# uC.net
KiCad netlist of a schematic drawn in Altium Designer
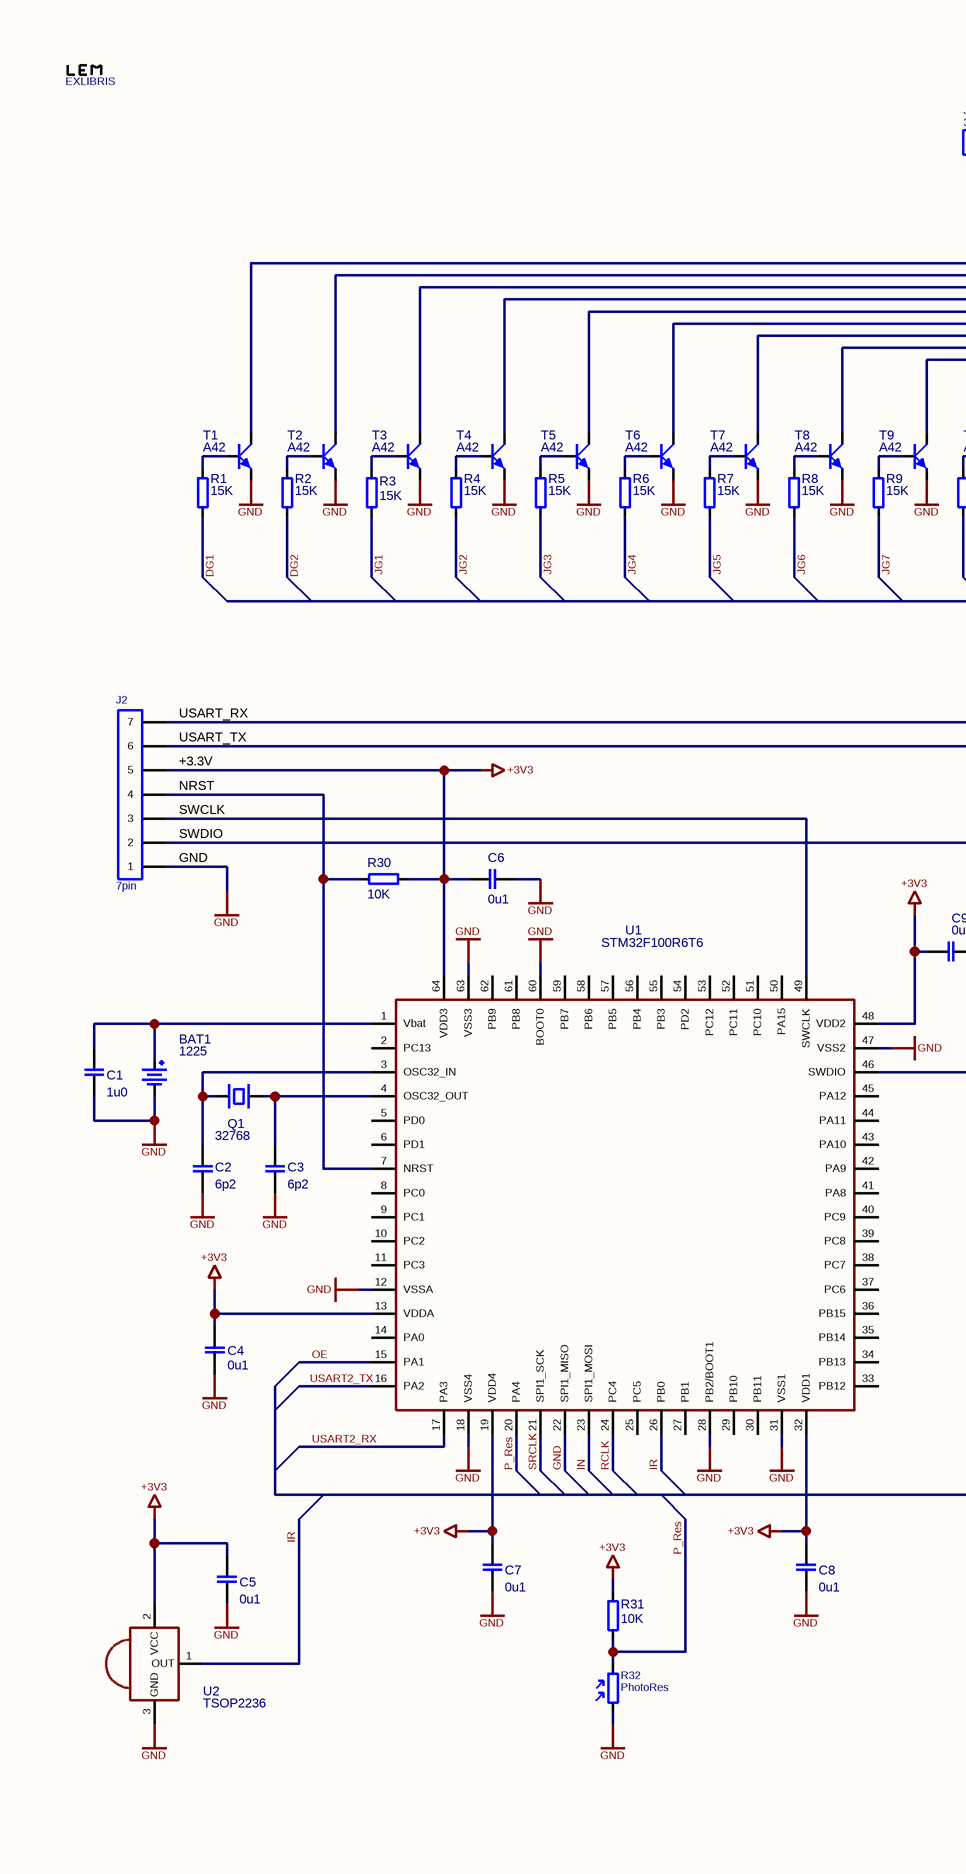
[diagram p0: uC.SchDoc, left]
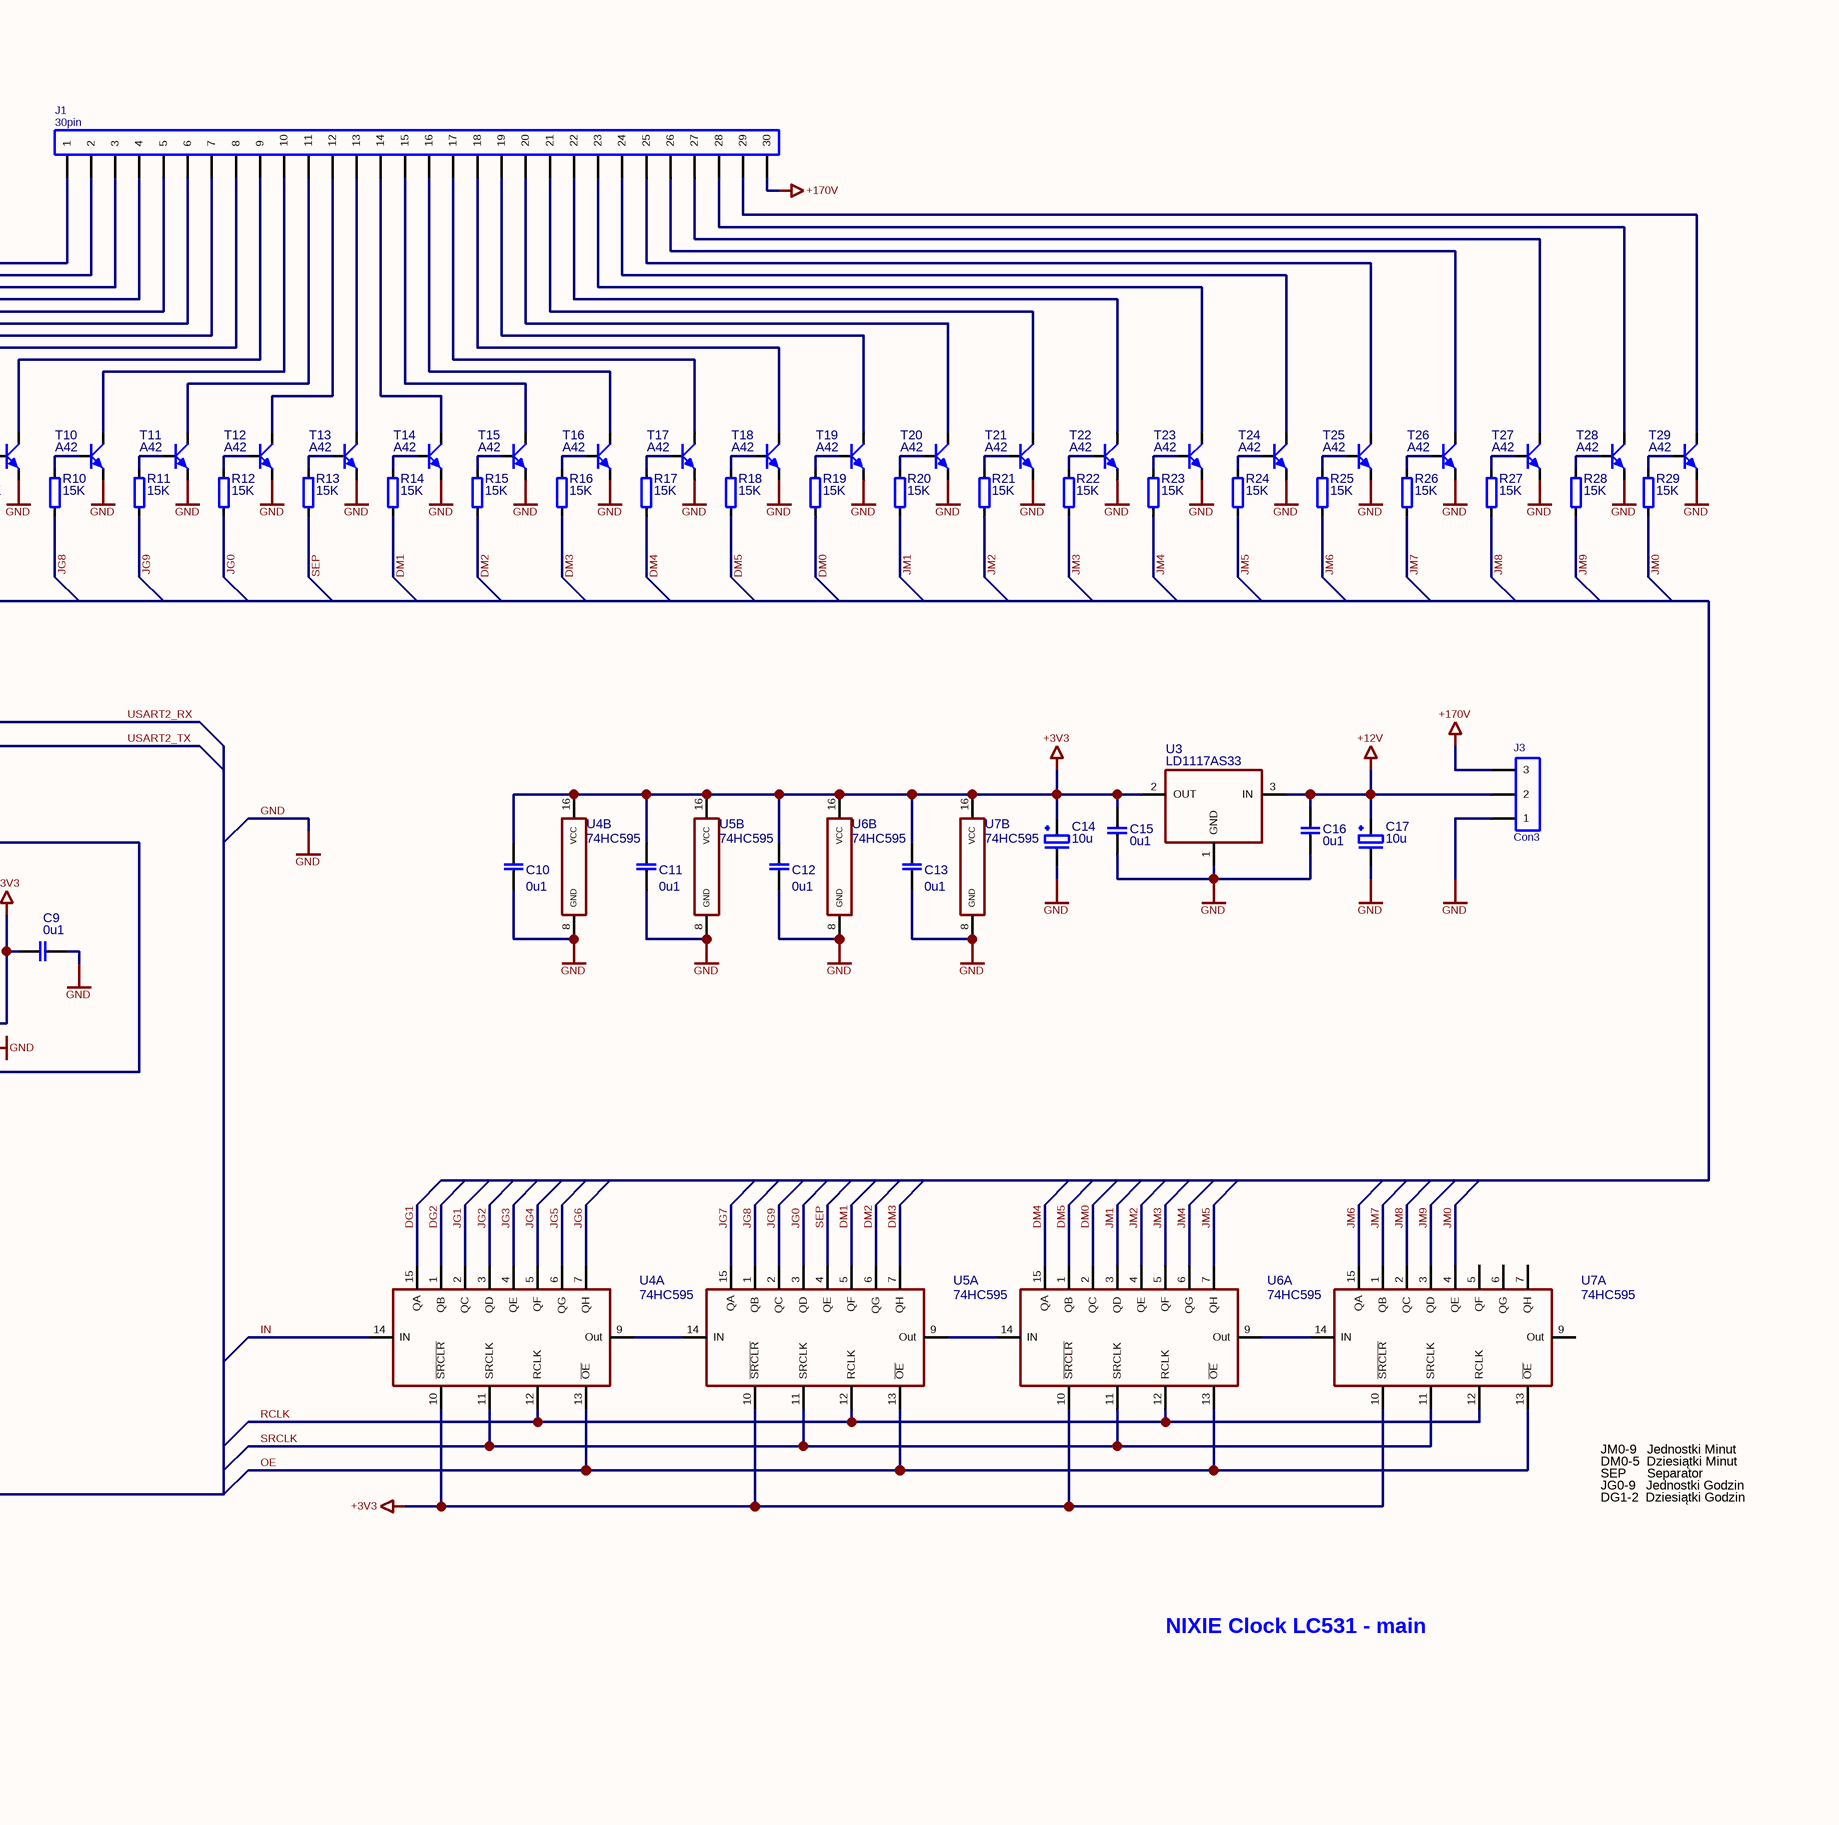
[diagram p1: uC.SchDoc, right]

(export (version "E")
  (design (tool "Eeschema 10.0.6"))
  (components
    (comp (ref "BAT1")
      (value "1225")
      (footprint "SMTU-1225")
      (description "Bateria Litowa 3V")
      (libsource (lib "Sch_Passive") (part "BAT_3V"))
    )
    (comp (ref "C1")
      (value "1u0")
      (footprint "C_SMD_0805")
      (description "Kondensator monolityczny")
      (libsource (lib "Caps") (part "C"))
    )
    (comp (ref "C2")
      (value "6p2")
      (footprint "C_SMD_0805")
      (description "Kondensator monolityczny")
      (libsource (lib "Caps") (part "C"))
    )
    (comp (ref "C3")
      (value "6p2")
      (footprint "C_SMD_0805")
      (description "Kondensator monolityczny")
      (libsource (lib "Caps") (part "C"))
    )
    (comp (ref "C4")
      (value "0u1")
      (footprint "C_SMD_0603")
      (description "Kondensator monolityczny")
      (libsource (lib "Caps") (part "C"))
    )
    (comp (ref "C5")
      (value "0u1")
      (footprint "C_SMD_0603")
      (description "Kondensator monolityczny")
      (libsource (lib "Caps") (part "C"))
    )
    (comp (ref "C6")
      (value "0u1")
      (footprint "C_SMD_0603")
      (description "Kondensator monolityczny")
      (libsource (lib "Caps") (part "C"))
    )
    (comp (ref "C7")
      (value "0u1")
      (footprint "C_SMD_0603")
      (description "Kondensator monolityczny")
      (libsource (lib "Caps") (part "C"))
    )
    (comp (ref "C8")
      (value "0u1")
      (footprint "C_SMD_0603")
      (description "Kondensator monolityczny")
      (libsource (lib "Caps") (part "C"))
    )
    (comp (ref "C9")
      (value "0u1")
      (footprint "C_SMD_0603")
      (description "Kondensator monolityczny")
      (libsource (lib "Caps") (part "C"))
    )
    (comp (ref "C10")
      (value "0u1")
      (footprint "C_SMD_0603")
      (description "Kondensator monolityczny")
      (libsource (lib "Caps") (part "C"))
    )
    (comp (ref "C11")
      (value "0u1")
      (footprint "C_SMD_0603")
      (description "Kondensator monolityczny")
      (libsource (lib "Caps") (part "C"))
    )
    (comp (ref "C12")
      (value "0u1")
      (footprint "C_SMD_0603")
      (description "Kondensator monolityczny")
      (libsource (lib "Caps") (part "C"))
    )
    (comp (ref "C13")
      (value "0u1")
      (footprint "C_SMD_0603")
      (description "Kondensator monolityczny")
      (libsource (lib "Caps") (part "C"))
    )
    (comp (ref "C14")
      (value "10u")
      (footprint "CE_T_SMC_6032_28")
      (description "Kondensator elektrolityczny")
      (libsource (lib "Caps") (part "CE"))
    )
    (comp (ref "C15")
      (value "0u1")
      (footprint "C_SMD_0603")
      (description "Kondensator monolityczny")
      (libsource (lib "Caps") (part "C"))
    )
    (comp (ref "C16")
      (value "0u1")
      (footprint "C_SMD_0603")
      (description "Kondensator monolityczny")
      (libsource (lib "Caps") (part "C"))
    )
    (comp (ref "C17")
      (value "10u")
      (footprint "CE_T_SMC_6032_28")
      (description "Kondensator elektrolityczny")
      (libsource (lib "Caps") (part "CE"))
    )
    (comp (ref "EXLIBRIS") (value "EXLIBRIS") (footprint "EXLBS_2") (libsource (lib "Misc") (part "EXLBR")))
    (comp (ref "J1") (value "30pin") (footprint "SIL30") (libsource (lib "Connectors") (part "CON 30pin")))
    (comp (ref "J2")
      (value "7pin")
      (footprint "SIL7_SMD_Horizontal")
      (description "Connector 7pin")
      (libsource (lib "Connectors") (part "CON 7pin"))
    )
    (comp (ref "J3")
      (value "Con3")
      (footprint "TE_147323-2")
      (description "Connector 3pin")
      (libsource (lib "Connectors") (part "CON 3pin"))
    )
    (comp (ref "Q1")
      (value "32768")
      (footprint "XTAL_3")
      (description "Rezonator kwarcowy")
      (libsource (lib "Sch_Passive") (part "Q"))
    )
    (comp (ref "R1")
      (value "15K")
      (footprint "R_SMD_0603")
      (description "Resistor")
      (libsource (lib "Res") (part "R"))
    )
    (comp (ref "R2")
      (value "15K")
      (footprint "R_SMD_0603")
      (description "Resistor")
      (libsource (lib "Res") (part "R"))
    )
    (comp (ref "R3")
      (value "15K")
      (footprint "R_SMD_0603")
      (description "Resistor")
      (libsource (lib "Res") (part "R"))
    )
    (comp (ref "R4")
      (value "15K")
      (footprint "R_SMD_0603")
      (description "Resistor")
      (libsource (lib "Res") (part "R"))
    )
    (comp (ref "R5")
      (value "15K")
      (footprint "R_SMD_0603")
      (description "Resistor")
      (libsource (lib "Res") (part "R"))
    )
    (comp (ref "R6")
      (value "15K")
      (footprint "R_SMD_0603")
      (description "Resistor")
      (libsource (lib "Res") (part "R"))
    )
    (comp (ref "R7")
      (value "15K")
      (footprint "R_SMD_0603")
      (description "Resistor")
      (libsource (lib "Res") (part "R"))
    )
    (comp (ref "R8")
      (value "15K")
      (footprint "R_SMD_0603")
      (description "Resistor")
      (libsource (lib "Res") (part "R"))
    )
    (comp (ref "R9")
      (value "15K")
      (footprint "R_SMD_0603")
      (description "Resistor")
      (libsource (lib "Res") (part "R"))
    )
    (comp (ref "R10")
      (value "15K")
      (footprint "R_SMD_0603")
      (description "Resistor")
      (libsource (lib "Res") (part "R"))
    )
    (comp (ref "R11")
      (value "15K")
      (footprint "R_SMD_0603")
      (description "Resistor")
      (libsource (lib "Res") (part "R"))
    )
    (comp (ref "R12")
      (value "15K")
      (footprint "R_SMD_0603")
      (description "Resistor")
      (libsource (lib "Res") (part "R"))
    )
    (comp (ref "R13")
      (value "15K")
      (footprint "R_SMD_0603")
      (description "Resistor")
      (libsource (lib "Res") (part "R"))
    )
    (comp (ref "R14")
      (value "15K")
      (footprint "R_SMD_0603")
      (description "Resistor")
      (libsource (lib "Res") (part "R"))
    )
    (comp (ref "R15")
      (value "15K")
      (footprint "R_SMD_0603")
      (description "Resistor")
      (libsource (lib "Res") (part "R"))
    )
    (comp (ref "R16")
      (value "15K")
      (footprint "R_SMD_0603")
      (description "Resistor")
      (libsource (lib "Res") (part "R"))
    )
    (comp (ref "R17")
      (value "15K")
      (footprint "R_SMD_0603")
      (description "Resistor")
      (libsource (lib "Res") (part "R"))
    )
    (comp (ref "R18")
      (value "15K")
      (footprint "R_SMD_0603")
      (description "Resistor")
      (libsource (lib "Res") (part "R"))
    )
    (comp (ref "R19")
      (value "15K")
      (footprint "R_SMD_0603")
      (description "Resistor")
      (libsource (lib "Res") (part "R"))
    )
    (comp (ref "R20")
      (value "15K")
      (footprint "R_SMD_0603")
      (description "Resistor")
      (libsource (lib "Res") (part "R"))
    )
    (comp (ref "R21")
      (value "15K")
      (footprint "R_SMD_0603")
      (description "Resistor")
      (libsource (lib "Res") (part "R"))
    )
    (comp (ref "R22")
      (value "15K")
      (footprint "R_SMD_0603")
      (description "Resistor")
      (libsource (lib "Res") (part "R"))
    )
    (comp (ref "R23")
      (value "15K")
      (footprint "R_SMD_0603")
      (description "Resistor")
      (libsource (lib "Res") (part "R"))
    )
    (comp (ref "R24")
      (value "15K")
      (footprint "R_SMD_0603")
      (description "Resistor")
      (libsource (lib "Res") (part "R"))
    )
    (comp (ref "R25")
      (value "15K")
      (footprint "R_SMD_0603")
      (description "Resistor")
      (libsource (lib "Res") (part "R"))
    )
    (comp (ref "R26")
      (value "15K")
      (footprint "R_SMD_0603")
      (description "Resistor")
      (libsource (lib "Res") (part "R"))
    )
    (comp (ref "R27")
      (value "15K")
      (footprint "R_SMD_0603")
      (description "Resistor")
      (libsource (lib "Res") (part "R"))
    )
    (comp (ref "R28")
      (value "15K")
      (footprint "R_SMD_0603")
      (description "Resistor")
      (libsource (lib "Res") (part "R"))
    )
    (comp (ref "R29")
      (value "15K")
      (footprint "R_SMD_0603")
      (description "Resistor")
      (libsource (lib "Res") (part "R"))
    )
    (comp (ref "R30")
      (value "10K")
      (footprint "R_SMD_0603")
      (description "Resistor")
      (libsource (lib "Res") (part "R"))
    )
    (comp (ref "R31")
      (value "10K")
      (footprint "R_SMD_0603")
      (description "Resistor")
      (libsource (lib "Res") (part "R"))
    )
    (comp (ref "R32")
      (value "PhotoRes")
      (footprint "R_Photo_V")
      (description "Photo resistor")
      (libsource (lib "RLCDQ") (part "R_Ph"))
    )
    (comp (ref "T1")
      (value "A42")
      (footprint "SOT-23 - Basic")
      (description "High Voltage NPN transistor")
      (libsource (lib "Tranzystory") (part "MMBTA42"))
    )
    (comp (ref "T2")
      (value "A42")
      (footprint "SOT-23 - Basic")
      (description "High Voltage NPN transistor")
      (libsource (lib "Tranzystory") (part "MMBTA42"))
    )
    (comp (ref "T3")
      (value "A42")
      (footprint "SOT-23 - Basic")
      (description "High Voltage NPN transistor")
      (libsource (lib "Tranzystory") (part "MMBTA42"))
    )
    (comp (ref "T4")
      (value "A42")
      (footprint "SOT-23 - Basic")
      (description "High Voltage NPN transistor")
      (libsource (lib "Tranzystory") (part "MMBTA42"))
    )
    (comp (ref "T5")
      (value "A42")
      (footprint "SOT-23 - Basic")
      (description "High Voltage NPN transistor")
      (libsource (lib "Tranzystory") (part "MMBTA42"))
    )
    (comp (ref "T6")
      (value "A42")
      (footprint "SOT-23 - Basic")
      (description "High Voltage NPN transistor")
      (libsource (lib "Tranzystory") (part "MMBTA42"))
    )
    (comp (ref "T7")
      (value "A42")
      (footprint "SOT-23 - Basic")
      (description "High Voltage NPN transistor")
      (libsource (lib "Tranzystory") (part "MMBTA42"))
    )
    (comp (ref "T8")
      (value "A42")
      (footprint "SOT-23 - Basic")
      (description "High Voltage NPN transistor")
      (libsource (lib "Tranzystory") (part "MMBTA42"))
    )
    (comp (ref "T9")
      (value "A42")
      (footprint "SOT-23 - Basic")
      (description "High Voltage NPN transistor")
      (libsource (lib "Tranzystory") (part "MMBTA42"))
    )
    (comp (ref "T10")
      (value "A42")
      (footprint "SOT-23 - Basic")
      (description "High Voltage NPN transistor")
      (libsource (lib "Tranzystory") (part "MMBTA42"))
    )
    (comp (ref "T11")
      (value "A42")
      (footprint "SOT-23 - Basic")
      (description "High Voltage NPN transistor")
      (libsource (lib "Tranzystory") (part "MMBTA42"))
    )
    (comp (ref "T12")
      (value "A42")
      (footprint "SOT-23 - Basic")
      (description "High Voltage NPN transistor")
      (libsource (lib "Tranzystory") (part "MMBTA42"))
    )
    (comp (ref "T13")
      (value "A42")
      (footprint "SOT-23 - Basic")
      (description "High Voltage NPN transistor")
      (libsource (lib "Tranzystory") (part "MMBTA42"))
    )
    (comp (ref "T14")
      (value "A42")
      (footprint "SOT-23 - Basic")
      (description "High Voltage NPN transistor")
      (libsource (lib "Tranzystory") (part "MMBTA42"))
    )
    (comp (ref "T15")
      (value "A42")
      (footprint "SOT-23 - Basic")
      (description "High Voltage NPN transistor")
      (libsource (lib "Tranzystory") (part "MMBTA42"))
    )
    (comp (ref "T16")
      (value "A42")
      (footprint "SOT-23 - Basic")
      (description "High Voltage NPN transistor")
      (libsource (lib "Tranzystory") (part "MMBTA42"))
    )
    (comp (ref "T17")
      (value "A42")
      (footprint "SOT-23 - Basic")
      (description "High Voltage NPN transistor")
      (libsource (lib "Tranzystory") (part "MMBTA42"))
    )
    (comp (ref "T18")
      (value "A42")
      (footprint "SOT-23 - Basic")
      (description "High Voltage NPN transistor")
      (libsource (lib "Tranzystory") (part "MMBTA42"))
    )
    (comp (ref "T19")
      (value "A42")
      (footprint "SOT-23 - Basic")
      (description "High Voltage NPN transistor")
      (libsource (lib "Tranzystory") (part "MMBTA42"))
    )
    (comp (ref "T20")
      (value "A42")
      (footprint "SOT-23 - Basic")
      (description "High Voltage NPN transistor")
      (libsource (lib "Tranzystory") (part "MMBTA42"))
    )
    (comp (ref "T21")
      (value "A42")
      (footprint "SOT-23 - Basic")
      (description "High Voltage NPN transistor")
      (libsource (lib "Tranzystory") (part "MMBTA42"))
    )
    (comp (ref "T22")
      (value "A42")
      (footprint "SOT-23 - Basic")
      (description "High Voltage NPN transistor")
      (libsource (lib "Tranzystory") (part "MMBTA42"))
    )
    (comp (ref "T23")
      (value "A42")
      (footprint "SOT-23 - Basic")
      (description "High Voltage NPN transistor")
      (libsource (lib "Tranzystory") (part "MMBTA42"))
    )
    (comp (ref "T24")
      (value "A42")
      (footprint "SOT-23 - Basic")
      (description "High Voltage NPN transistor")
      (libsource (lib "Tranzystory") (part "MMBTA42"))
    )
    (comp (ref "T25")
      (value "A42")
      (footprint "SOT-23 - Basic")
      (description "High Voltage NPN transistor")
      (libsource (lib "Tranzystory") (part "MMBTA42"))
    )
    (comp (ref "T26")
      (value "A42")
      (footprint "SOT-23 - Basic")
      (description "High Voltage NPN transistor")
      (libsource (lib "Tranzystory") (part "MMBTA42"))
    )
    (comp (ref "T27")
      (value "A42")
      (footprint "SOT-23 - Basic")
      (description "High Voltage NPN transistor")
      (libsource (lib "Tranzystory") (part "MMBTA42"))
    )
    (comp (ref "T28")
      (value "A42")
      (footprint "SOT-23 - Basic")
      (description "High Voltage NPN transistor")
      (libsource (lib "Tranzystory") (part "MMBTA42"))
    )
    (comp (ref "T29")
      (value "A42")
      (footprint "SOT-23 - Basic")
      (description "High Voltage NPN transistor")
      (libsource (lib "Tranzystory") (part "MMBTA42"))
    )
    (comp (ref "U1")
      (value "STM32F100R6T6")
      (footprint "LQFP-674")
      (libsource (lib "uC") (part "STM32F100R6T6"))
    )
    (comp (ref "U2") (value "TSOP2236") (footprint "TSOP-2236") (libsource (lib "uC") (part "IR Reciver")))
    (comp (ref "U3") (value "LD1117AS33") (footprint "SOT-223") (libsource (lib "uC") (part "AMS1117_3V3")))
    (comp (ref "U4")
      (value "74HC595")
      (footprint "SO-16_150")
      (description "8-bit shift registers with 3-state output")
      (libsource (lib "uC") (part "74595"))
    )
    (comp (ref "U5")
      (value "74HC595")
      (footprint "SO-16_150")
      (description "8-bit shift registers with 3-state output")
      (libsource (lib "uC") (part "74595"))
    )
    (comp (ref "U6")
      (value "74HC595")
      (footprint "SO-16_150")
      (description "8-bit shift registers with 3-state output")
      (libsource (lib "uC") (part "74595"))
    )
    (comp (ref "U7")
      (value "74HC595")
      (footprint "SO-16_150")
      (description "8-bit shift registers with 3-state output")
      (libsource (lib "uC") (part "74595"))
    )
  )
  (nets
    (net (code "1") (name "+3V3") (class "Default")
      (node (ref "C10") (pin "2") (pinfunction "2_2") (pintype "passive"))
      (node (ref "C11") (pin "2") (pinfunction "2_2") (pintype "passive"))
      (node (ref "C12") (pin "2") (pinfunction "2_2") (pintype "passive"))
      (node (ref "C13") (pin "2") (pinfunction "2_2") (pintype "passive"))
      (node (ref "C14") (pin "2") (pinfunction "+_2") (pintype "passive"))
      (node (ref "C15") (pin "2") (pinfunction "2_2") (pintype "passive"))
      (node (ref "C4") (pin "1") (pinfunction "1_1") (pintype "passive"))
      (node (ref "C5") (pin "2") (pinfunction "2_2") (pintype "passive"))
      (node (ref "C6") (pin "2") (pinfunction "2_2") (pintype "passive"))
      (node (ref "C7") (pin "2") (pinfunction "2_2") (pintype "passive"))
      (node (ref "C8") (pin "2") (pinfunction "2_2") (pintype "passive"))
      (node (ref "C9") (pin "1") (pinfunction "1_1") (pintype "passive"))
      (node (ref "J2") (pin "5") (pinfunction "5_5") (pintype "passive"))
      (node (ref "R30") (pin "1") (pinfunction "1_1") (pintype "passive"))
      (node (ref "R31") (pin "1") (pinfunction "1_1") (pintype "passive"))
      (node (ref "U1") (pin "13") (pinfunction "VDDA_13") (pintype "passive"))
      (node (ref "U1") (pin "19") (pinfunction "VDD4_19") (pintype "passive"))
      (node (ref "U1") (pin "32") (pinfunction "VDD1_32") (pintype "passive"))
      (node (ref "U1") (pin "48") (pinfunction "VDD2_48") (pintype "passive"))
      (node (ref "U1") (pin "64") (pinfunction "VDD3_64") (pintype "passive"))
      (node (ref "U2") (pin "2") (pinfunction "VCC_2") (pintype "passive"))
      (node (ref "U3") (pin "2") (pinfunction "OUT_2") (pintype "passive"))
      (node (ref "U4") (pin "10") (pinfunction "~{SRCLR}_10") (pintype "passive"))
      (node (ref "U4") (pin "16") (pinfunction "VCC_16") (pintype "passive"))
      (node (ref "U5") (pin "10") (pinfunction "~{SRCLR}_10") (pintype "passive"))
      (node (ref "U5") (pin "16") (pinfunction "VCC_16") (pintype "passive"))
      (node (ref "U6") (pin "10") (pinfunction "~{SRCLR}_10") (pintype "passive"))
      (node (ref "U6") (pin "16") (pinfunction "VCC_16") (pintype "passive"))
      (node (ref "U7") (pin "10") (pinfunction "~{SRCLR}_10") (pintype "passive"))
      (node (ref "U7") (pin "16") (pinfunction "VCC_16") (pintype "passive"))
    )
    (net (code "2") (name "+12V") (class "Default")
      (node (ref "C16") (pin "2") (pinfunction "2_2") (pintype "passive"))
      (node (ref "C17") (pin "2") (pinfunction "+_2") (pintype "passive"))
      (node (ref "J3") (pin "2") (pinfunction "2_2") (pintype "passive"))
      (node (ref "U3") (pin "3") (pinfunction "IN_3") (pintype "passive"))
    )
    (net (code "3") (name "+170V") (class "Default")
      (node (ref "J1") (pin "30") (pinfunction "30_30") (pintype "passive"))
      (node (ref "J3") (pin "3") (pinfunction "3_3") (pintype "passive"))
    )
    (net (code "4") (name "/DG1") (class "Default")
      (node (ref "R1") (pin "1") (pinfunction "1_1") (pintype "passive"))
      (node (ref "U4") (pin "15") (pinfunction "QA_15") (pintype "passive"))
    )
    (net (code "5") (name "/DG2") (class "Default")
      (node (ref "R2") (pin "1") (pinfunction "1_1") (pintype "passive"))
      (node (ref "U4") (pin "1") (pinfunction "QB_1") (pintype "passive"))
    )
    (net (code "6") (name "/DM0") (class "Default")
      (node (ref "R19") (pin "1") (pinfunction "1_1") (pintype "passive"))
      (node (ref "U6") (pin "2") (pinfunction "QC_2") (pintype "passive"))
    )
    (net (code "7") (name "/DM1") (class "Default")
      (node (ref "R14") (pin "1") (pinfunction "1_1") (pintype "passive"))
      (node (ref "U5") (pin "5") (pinfunction "QF_5") (pintype "passive"))
    )
    (net (code "8") (name "/DM2") (class "Default")
      (node (ref "R15") (pin "1") (pinfunction "1_1") (pintype "passive"))
      (node (ref "U5") (pin "6") (pinfunction "QG_6") (pintype "passive"))
    )
    (net (code "9") (name "/DM3") (class "Default")
      (node (ref "R16") (pin "1") (pinfunction "1_1") (pintype "passive"))
      (node (ref "U5") (pin "7") (pinfunction "QH_7") (pintype "passive"))
    )
    (net (code "10") (name "/DM4") (class "Default")
      (node (ref "R17") (pin "1") (pinfunction "1_1") (pintype "passive"))
      (node (ref "U6") (pin "15") (pinfunction "QA_15") (pintype "passive"))
    )
    (net (code "11") (name "/DM5") (class "Default")
      (node (ref "R18") (pin "2") (pinfunction "2_2") (pintype "passive"))
      (node (ref "U6") (pin "1") (pinfunction "QB_1") (pintype "passive"))
    )
    (net (code "12") (name "/IN") (class "Default")
      (node (ref "U1") (pin "23") (pinfunction "SPI1_MOSI_23") (pintype "passive"))
      (node (ref "U4") (pin "14") (pinfunction "IN_14") (pintype "passive"))
    )
    (net (code "13") (name "/IR") (class "Default")
      (node (ref "U1") (pin "26") (pinfunction "PB0_26") (pintype "passive"))
      (node (ref "U2") (pin "1") (pinfunction "OUT_1") (pintype "passive"))
    )
    (net (code "14") (name "/JG0") (class "Default")
      (node (ref "R12") (pin "1") (pinfunction "1_1") (pintype "passive"))
      (node (ref "U5") (pin "3") (pinfunction "QD_3") (pintype "passive"))
    )
    (net (code "15") (name "/JG1") (class "Default")
      (node (ref "R3") (pin "1") (pinfunction "1_1") (pintype "passive"))
      (node (ref "U4") (pin "2") (pinfunction "QC_2") (pintype "passive"))
    )
    (net (code "16") (name "/JG2") (class "Default")
      (node (ref "R4") (pin "1") (pinfunction "1_1") (pintype "passive"))
      (node (ref "U4") (pin "3") (pinfunction "QD_3") (pintype "passive"))
    )
    (net (code "17") (name "/JG3") (class "Default")
      (node (ref "R5") (pin "1") (pinfunction "1_1") (pintype "passive"))
      (node (ref "U4") (pin "4") (pinfunction "QE_4") (pintype "passive"))
    )
    (net (code "18") (name "/JG4") (class "Default")
      (node (ref "R6") (pin "1") (pinfunction "1_1") (pintype "passive"))
      (node (ref "U4") (pin "5") (pinfunction "QF_5") (pintype "passive"))
    )
    (net (code "19") (name "/JG5") (class "Default")
      (node (ref "R7") (pin "1") (pinfunction "1_1") (pintype "passive"))
      (node (ref "U4") (pin "6") (pinfunction "QG_6") (pintype "passive"))
    )
    (net (code "20") (name "/JG6") (class "Default")
      (node (ref "R8") (pin "2") (pinfunction "2_2") (pintype "passive"))
      (node (ref "U4") (pin "7") (pinfunction "QH_7") (pintype "passive"))
    )
    (net (code "21") (name "/JG7") (class "Default")
      (node (ref "R9") (pin "1") (pinfunction "1_1") (pintype "passive"))
      (node (ref "U5") (pin "15") (pinfunction "QA_15") (pintype "passive"))
    )
    (net (code "22") (name "/JG8") (class "Default")
      (node (ref "R10") (pin "1") (pinfunction "1_1") (pintype "passive"))
      (node (ref "U5") (pin "1") (pinfunction "QB_1") (pintype "passive"))
    )
    (net (code "23") (name "/JG9") (class "Default")
      (node (ref "R11") (pin "1") (pinfunction "1_1") (pintype "passive"))
      (node (ref "U5") (pin "2") (pinfunction "QC_2") (pintype "passive"))
    )
    (net (code "24") (name "/JM0") (class "Default")
      (node (ref "R29") (pin "1") (pinfunction "1_1") (pintype "passive"))
      (node (ref "U7") (pin "4") (pinfunction "QE_4") (pintype "passive"))
    )
    (net (code "25") (name "/JM1") (class "Default")
      (node (ref "R20") (pin "1") (pinfunction "1_1") (pintype "passive"))
      (node (ref "U6") (pin "3") (pinfunction "QD_3") (pintype "passive"))
    )
    (net (code "26") (name "/JM2") (class "Default")
      (node (ref "R21") (pin "1") (pinfunction "1_1") (pintype "passive"))
      (node (ref "U6") (pin "4") (pinfunction "QE_4") (pintype "passive"))
    )
    (net (code "27") (name "/JM3") (class "Default")
      (node (ref "R22") (pin "1") (pinfunction "1_1") (pintype "passive"))
      (node (ref "U6") (pin "5") (pinfunction "QF_5") (pintype "passive"))
    )
    (net (code "28") (name "/JM4") (class "Default")
      (node (ref "R23") (pin "2") (pinfunction "2_2") (pintype "passive"))
      (node (ref "U6") (pin "6") (pinfunction "QG_6") (pintype "passive"))
    )
    (net (code "29") (name "/JM5") (class "Default")
      (node (ref "R24") (pin "1") (pinfunction "1_1") (pintype "passive"))
      (node (ref "U6") (pin "7") (pinfunction "QH_7") (pintype "passive"))
    )
    (net (code "30") (name "/JM6") (class "Default")
      (node (ref "R25") (pin "1") (pinfunction "1_1") (pintype "passive"))
      (node (ref "U7") (pin "15") (pinfunction "QA_15") (pintype "passive"))
    )
    (net (code "31") (name "/JM7") (class "Default")
      (node (ref "R26") (pin "1") (pinfunction "1_1") (pintype "passive"))
      (node (ref "U7") (pin "1") (pinfunction "QB_1") (pintype "passive"))
    )
    (net (code "32") (name "/JM8") (class "Default")
      (node (ref "R27") (pin "1") (pinfunction "1_1") (pintype "passive"))
      (node (ref "U7") (pin "2") (pinfunction "QC_2") (pintype "passive"))
    )
    (net (code "33") (name "/JM9") (class "Default")
      (node (ref "R28") (pin "2") (pinfunction "2_2") (pintype "passive"))
      (node (ref "U7") (pin "3") (pinfunction "QD_3") (pintype "passive"))
    )
    (net (code "34") (name "/OE") (class "Default")
      (node (ref "U1") (pin "15") (pinfunction "PA1_15") (pintype "passive"))
      (node (ref "U4") (pin "13") (pinfunction "~{OE}_13") (pintype "passive"))
      (node (ref "U5") (pin "13") (pinfunction "~{OE}_13") (pintype "passive"))
      (node (ref "U6") (pin "13") (pinfunction "~{OE}_13") (pintype "passive"))
      (node (ref "U7") (pin "13") (pinfunction "~{OE}_13") (pintype "passive"))
    )
    (net (code "35") (name "/P_Res") (class "Default")
      (node (ref "R31") (pin "2") (pinfunction "2_2") (pintype "passive"))
      (node (ref "R32") (pin "1") (pinfunction "-_1") (pintype "passive"))
      (node (ref "U1") (pin "20") (pinfunction "PA4_20") (pintype "passive"))
    )
    (net (code "36") (name "/RCLK") (class "Default")
      (node (ref "U1") (pin "24") (pinfunction "PC4_24") (pintype "passive"))
      (node (ref "U4") (pin "12") (pinfunction "RCLK_12") (pintype "passive"))
      (node (ref "U5") (pin "12") (pinfunction "RCLK_12") (pintype "passive"))
      (node (ref "U6") (pin "12") (pinfunction "RCLK_12") (pintype "passive"))
      (node (ref "U7") (pin "12") (pinfunction "RCLK_12") (pintype "passive"))
    )
    (net (code "37") (name "/SEP") (class "Default")
      (node (ref "R13") (pin "2") (pinfunction "2_2") (pintype "passive"))
      (node (ref "U5") (pin "4") (pinfunction "QE_4") (pintype "passive"))
    )
    (net (code "38") (name "/SRCLK") (class "Default")
      (node (ref "U1") (pin "21") (pinfunction "SPI1_SCK_21") (pintype "passive"))
      (node (ref "U4") (pin "11") (pinfunction "SRCLK_11") (pintype "passive"))
      (node (ref "U5") (pin "11") (pinfunction "SRCLK_11") (pintype "passive"))
      (node (ref "U6") (pin "11") (pinfunction "SRCLK_11") (pintype "passive"))
      (node (ref "U7") (pin "11") (pinfunction "SRCLK_11") (pintype "passive"))
    )
    (net (code "39") (name "/USART2_RX") (class "Default")
      (node (ref "J2") (pin "7") (pinfunction "7_7") (pintype "passive"))
      (node (ref "U1") (pin "17") (pinfunction "PA3_17") (pintype "passive"))
    )
    (net (code "40") (name "/USART2_TX") (class "Default")
      (node (ref "J2") (pin "6") (pinfunction "6_6") (pintype "passive"))
      (node (ref "U1") (pin "16") (pinfunction "PA2_16") (pintype "passive"))
    )
    (net (code "41") (name "GND") (class "Default")
      (node (ref "BAT1") (pin "2") (pinfunction "-_2") (pintype "passive"))
      (node (ref "C1") (pin "1") (pinfunction "1_1") (pintype "passive"))
      (node (ref "C10") (pin "1") (pinfunction "1_1") (pintype "passive"))
      (node (ref "C11") (pin "1") (pinfunction "1_1") (pintype "passive"))
      (node (ref "C12") (pin "1") (pinfunction "1_1") (pintype "passive"))
      (node (ref "C13") (pin "1") (pinfunction "1_1") (pintype "passive"))
      (node (ref "C14") (pin "1") (pinfunction "-_1") (pintype "passive"))
      (node (ref "C15") (pin "1") (pinfunction "1_1") (pintype "passive"))
      (node (ref "C16") (pin "1") (pinfunction "1_1") (pintype "passive"))
      (node (ref "C17") (pin "1") (pinfunction "-_1") (pintype "passive"))
      (node (ref "C2") (pin "1") (pinfunction "1_1") (pintype "passive"))
      (node (ref "C3") (pin "1") (pinfunction "1_1") (pintype "passive"))
      (node (ref "C4") (pin "2") (pinfunction "2_2") (pintype "passive"))
      (node (ref "C5") (pin "1") (pinfunction "1_1") (pintype "passive"))
      (node (ref "C6") (pin "1") (pinfunction "1_1") (pintype "passive"))
      (node (ref "C7") (pin "1") (pinfunction "1_1") (pintype "passive"))
      (node (ref "C8") (pin "1") (pinfunction "1_1") (pintype "passive"))
      (node (ref "C9") (pin "2") (pinfunction "2_2") (pintype "passive"))
      (node (ref "J2") (pin "1") (pinfunction "1_1") (pintype "passive"))
      (node (ref "J3") (pin "1") (pinfunction "1_1") (pintype "passive"))
      (node (ref "R32") (pin "2") (pinfunction "+_2") (pintype "passive"))
      (node (ref "T1") (pin "2") (pinfunction "Emitter_2") (pintype "passive"))
      (node (ref "T10") (pin "2") (pinfunction "Emitter_2") (pintype "passive"))
      (node (ref "T11") (pin "2") (pinfunction "Emitter_2") (pintype "passive"))
      (node (ref "T12") (pin "2") (pinfunction "Emitter_2") (pintype "passive"))
      (node (ref "T13") (pin "2") (pinfunction "Emitter_2") (pintype "passive"))
      (node (ref "T14") (pin "2") (pinfunction "Emitter_2") (pintype "passive"))
      (node (ref "T15") (pin "2") (pinfunction "Emitter_2") (pintype "passive"))
      (node (ref "T16") (pin "2") (pinfunction "Emitter_2") (pintype "passive"))
      (node (ref "T17") (pin "2") (pinfunction "Emitter_2") (pintype "passive"))
      (node (ref "T18") (pin "2") (pinfunction "Emitter_2") (pintype "passive"))
      (node (ref "T19") (pin "2") (pinfunction "Emitter_2") (pintype "passive"))
      (node (ref "T2") (pin "2") (pinfunction "Emitter_2") (pintype "passive"))
      (node (ref "T20") (pin "2") (pinfunction "Emitter_2") (pintype "passive"))
      (node (ref "T21") (pin "2") (pinfunction "Emitter_2") (pintype "passive"))
      (node (ref "T22") (pin "2") (pinfunction "Emitter_2") (pintype "passive"))
      (node (ref "T23") (pin "2") (pinfunction "Emitter_2") (pintype "passive"))
      (node (ref "T24") (pin "2") (pinfunction "Emitter_2") (pintype "passive"))
      (node (ref "T25") (pin "2") (pinfunction "Emitter_2") (pintype "passive"))
      (node (ref "T26") (pin "2") (pinfunction "Emitter_2") (pintype "passive"))
      (node (ref "T27") (pin "2") (pinfunction "Emitter_2") (pintype "passive"))
      (node (ref "T28") (pin "2") (pinfunction "Emitter_2") (pintype "passive"))
      (node (ref "T29") (pin "2") (pinfunction "Emitter_2") (pintype "passive"))
      (node (ref "T3") (pin "2") (pinfunction "Emitter_2") (pintype "passive"))
      (node (ref "T4") (pin "2") (pinfunction "Emitter_2") (pintype "passive"))
      (node (ref "T5") (pin "2") (pinfunction "Emitter_2") (pintype "passive"))
      (node (ref "T6") (pin "2") (pinfunction "Emitter_2") (pintype "passive"))
      (node (ref "T7") (pin "2") (pinfunction "Emitter_2") (pintype "passive"))
      (node (ref "T8") (pin "2") (pinfunction "Emitter_2") (pintype "passive"))
      (node (ref "T9") (pin "2") (pinfunction "Emitter_2") (pintype "passive"))
      (node (ref "U1") (pin "12") (pinfunction "VSSA_12") (pintype "passive"))
      (node (ref "U1") (pin "18") (pinfunction "VSS4_18") (pintype "passive"))
      (node (ref "U1") (pin "22") (pinfunction "SPI1_MISO_22") (pintype "passive"))
      (node (ref "U1") (pin "28") (pinfunction "PB2/BOOT1_28") (pintype "passive"))
      (node (ref "U1") (pin "31") (pinfunction "VSS1_31") (pintype "passive"))
      (node (ref "U1") (pin "47") (pinfunction "VSS2_47") (pintype "passive"))
      (node (ref "U1") (pin "60") (pinfunction "BOOT0_60") (pintype "passive"))
      (node (ref "U1") (pin "63") (pinfunction "VSS3_63") (pintype "passive"))
      (node (ref "U2") (pin "3") (pinfunction "GND_3") (pintype "passive"))
      (node (ref "U3") (pin "1") (pinfunction "GND_1") (pintype "passive"))
      (node (ref "U4") (pin "8") (pinfunction "GND_8") (pintype "power_in"))
      (node (ref "U5") (pin "8") (pinfunction "GND_8") (pintype "power_in"))
      (node (ref "U6") (pin "8") (pinfunction "GND_8") (pintype "power_in"))
      (node (ref "U7") (pin "8") (pinfunction "GND_8") (pintype "power_in"))
    )
    (net (code "42") (name "Net-(BAT1-+)") (class "Default")
      (node (ref "BAT1") (pin "1") (pinfunction "+_1") (pintype "passive"))
      (node (ref "C1") (pin "2") (pinfunction "2_2") (pintype "passive"))
      (node (ref "U1") (pin "1") (pinfunction "Vbat_1") (pintype "passive"))
    )
    (net (code "43") (name "Net-(T1-Base)") (class "Default")
      (node (ref "R1") (pin "2") (pinfunction "2_2") (pintype "passive"))
      (node (ref "T1") (pin "1") (pinfunction "Base_1") (pintype "passive"))
    )
    (net (code "44") (name "Net-(T1-Collector)") (class "Default")
      (node (ref "J1") (pin "1") (pinfunction "1_1") (pintype "passive"))
      (node (ref "T1") (pin "3") (pinfunction "Collector_3") (pintype "passive"))
    )
    (net (code "45") (name "Net-(T2-Base)") (class "Default")
      (node (ref "R2") (pin "2") (pinfunction "2_2") (pintype "passive"))
      (node (ref "T2") (pin "1") (pinfunction "Base_1") (pintype "passive"))
    )
    (net (code "46") (name "Net-(T2-Collector)") (class "Default")
      (node (ref "J1") (pin "2") (pinfunction "2_2") (pintype "passive"))
      (node (ref "T2") (pin "3") (pinfunction "Collector_3") (pintype "passive"))
    )
    (net (code "47") (name "Net-(T3-Base)") (class "Default")
      (node (ref "R3") (pin "2") (pinfunction "2_2") (pintype "passive"))
      (node (ref "T3") (pin "1") (pinfunction "Base_1") (pintype "passive"))
    )
    (net (code "48") (name "Net-(T3-Collector)") (class "Default")
      (node (ref "J1") (pin "3") (pinfunction "3_3") (pintype "passive"))
      (node (ref "T3") (pin "3") (pinfunction "Collector_3") (pintype "passive"))
    )
    (net (code "49") (name "Net-(T4-Base)") (class "Default")
      (node (ref "R4") (pin "2") (pinfunction "2_2") (pintype "passive"))
      (node (ref "T4") (pin "1") (pinfunction "Base_1") (pintype "passive"))
    )
    (net (code "50") (name "Net-(T4-Collector)") (class "Default")
      (node (ref "J1") (pin "4") (pinfunction "4_4") (pintype "passive"))
      (node (ref "T4") (pin "3") (pinfunction "Collector_3") (pintype "passive"))
    )
    (net (code "51") (name "Net-(T5-Base)") (class "Default")
      (node (ref "R5") (pin "2") (pinfunction "2_2") (pintype "passive"))
      (node (ref "T5") (pin "1") (pinfunction "Base_1") (pintype "passive"))
    )
    (net (code "52") (name "Net-(T5-Collector)") (class "Default")
      (node (ref "J1") (pin "5") (pinfunction "5_5") (pintype "passive"))
      (node (ref "T5") (pin "3") (pinfunction "Collector_3") (pintype "passive"))
    )
    (net (code "53") (name "Net-(T6-Base)") (class "Default")
      (node (ref "R6") (pin "2") (pinfunction "2_2") (pintype "passive"))
      (node (ref "T6") (pin "1") (pinfunction "Base_1") (pintype "passive"))
    )
    (net (code "54") (name "Net-(T6-Collector)") (class "Default")
      (node (ref "J1") (pin "6") (pinfunction "6_6") (pintype "passive"))
      (node (ref "T6") (pin "3") (pinfunction "Collector_3") (pintype "passive"))
    )
    (net (code "55") (name "Net-(T7-Base)") (class "Default")
      (node (ref "R7") (pin "2") (pinfunction "2_2") (pintype "passive"))
      (node (ref "T7") (pin "1") (pinfunction "Base_1") (pintype "passive"))
    )
    (net (code "56") (name "Net-(T7-Collector)") (class "Default")
      (node (ref "J1") (pin "7") (pinfunction "7_7") (pintype "passive"))
      (node (ref "T7") (pin "3") (pinfunction "Collector_3") (pintype "passive"))
    )
    (net (code "57") (name "Net-(T8-Base)") (class "Default")
      (node (ref "R8") (pin "1") (pinfunction "1_1") (pintype "passive"))
      (node (ref "T8") (pin "1") (pinfunction "Base_1") (pintype "passive"))
    )
    (net (code "58") (name "Net-(T8-Collector)") (class "Default")
      (node (ref "J1") (pin "8") (pinfunction "8_8") (pintype "passive"))
      (node (ref "T8") (pin "3") (pinfunction "Collector_3") (pintype "passive"))
    )
    (net (code "59") (name "Net-(T9-Base)") (class "Default")
      (node (ref "R9") (pin "2") (pinfunction "2_2") (pintype "passive"))
      (node (ref "T9") (pin "1") (pinfunction "Base_1") (pintype "passive"))
    )
    (net (code "60") (name "Net-(T9-Collector)") (class "Default")
      (node (ref "J1") (pin "9") (pinfunction "9_9") (pintype "passive"))
      (node (ref "T9") (pin "3") (pinfunction "Collector_3") (pintype "passive"))
    )
    (net (code "61") (name "Net-(T10-Base)") (class "Default")
      (node (ref "R10") (pin "2") (pinfunction "2_2") (pintype "passive"))
      (node (ref "T10") (pin "1") (pinfunction "Base_1") (pintype "passive"))
    )
    (net (code "62") (name "Net-(T10-Collector)") (class "Default")
      (node (ref "J1") (pin "10") (pinfunction "10_10") (pintype "passive"))
      (node (ref "T10") (pin "3") (pinfunction "Collector_3") (pintype "passive"))
    )
    (net (code "63") (name "Net-(T11-Base)") (class "Default")
      (node (ref "R11") (pin "2") (pinfunction "2_2") (pintype "passive"))
      (node (ref "T11") (pin "1") (pinfunction "Base_1") (pintype "passive"))
    )
    (net (code "64") (name "Net-(T11-Collector)") (class "Default")
      (node (ref "J1") (pin "11") (pinfunction "11_11") (pintype "passive"))
      (node (ref "T11") (pin "3") (pinfunction "Collector_3") (pintype "passive"))
    )
    (net (code "65") (name "Net-(T12-Base)") (class "Default")
      (node (ref "R12") (pin "2") (pinfunction "2_2") (pintype "passive"))
      (node (ref "T12") (pin "1") (pinfunction "Base_1") (pintype "passive"))
    )
    (net (code "66") (name "Net-(T12-Collector)") (class "Default")
      (node (ref "J1") (pin "12") (pinfunction "12_12") (pintype "passive"))
      (node (ref "T12") (pin "3") (pinfunction "Collector_3") (pintype "passive"))
    )
    (net (code "67") (name "Net-(T13-Base)") (class "Default")
      (node (ref "R13") (pin "1") (pinfunction "1_1") (pintype "passive"))
      (node (ref "T13") (pin "1") (pinfunction "Base_1") (pintype "passive"))
    )
    (net (code "68") (name "Net-(T13-Collector)") (class "Default")
      (node (ref "J1") (pin "13") (pinfunction "13_13") (pintype "passive"))
      (node (ref "T13") (pin "3") (pinfunction "Collector_3") (pintype "passive"))
    )
    (net (code "69") (name "Net-(T14-Base)") (class "Default")
      (node (ref "R14") (pin "2") (pinfunction "2_2") (pintype "passive"))
      (node (ref "T14") (pin "1") (pinfunction "Base_1") (pintype "passive"))
    )
    (net (code "70") (name "Net-(T14-Collector)") (class "Default")
      (node (ref "J1") (pin "14") (pinfunction "14_14") (pintype "passive"))
      (node (ref "T14") (pin "3") (pinfunction "Collector_3") (pintype "passive"))
    )
    (net (code "71") (name "Net-(T15-Base)") (class "Default")
      (node (ref "R15") (pin "2") (pinfunction "2_2") (pintype "passive"))
      (node (ref "T15") (pin "1") (pinfunction "Base_1") (pintype "passive"))
    )
    (net (code "72") (name "Net-(T15-Collector)") (class "Default")
      (node (ref "J1") (pin "15") (pinfunction "15_15") (pintype "passive"))
      (node (ref "T15") (pin "3") (pinfunction "Collector_3") (pintype "passive"))
    )
    (net (code "73") (name "Net-(T16-Base)") (class "Default")
      (node (ref "R16") (pin "2") (pinfunction "2_2") (pintype "passive"))
      (node (ref "T16") (pin "1") (pinfunction "Base_1") (pintype "passive"))
    )
    (net (code "74") (name "Net-(T16-Collector)") (class "Default")
      (node (ref "J1") (pin "16") (pinfunction "16_16") (pintype "passive"))
      (node (ref "T16") (pin "3") (pinfunction "Collector_3") (pintype "passive"))
    )
    (net (code "75") (name "Net-(T17-Base)") (class "Default")
      (node (ref "R17") (pin "2") (pinfunction "2_2") (pintype "passive"))
      (node (ref "T17") (pin "1") (pinfunction "Base_1") (pintype "passive"))
    )
    (net (code "76") (name "Net-(T17-Collector)") (class "Default")
      (node (ref "J1") (pin "17") (pinfunction "17_17") (pintype "passive"))
      (node (ref "T17") (pin "3") (pinfunction "Collector_3") (pintype "passive"))
    )
    (net (code "77") (name "Net-(T18-Base)") (class "Default")
      (node (ref "R18") (pin "1") (pinfunction "1_1") (pintype "passive"))
      (node (ref "T18") (pin "1") (pinfunction "Base_1") (pintype "passive"))
    )
    (net (code "78") (name "Net-(T18-Collector)") (class "Default")
      (node (ref "J1") (pin "18") (pinfunction "18_18") (pintype "passive"))
      (node (ref "T18") (pin "3") (pinfunction "Collector_3") (pintype "passive"))
    )
    (net (code "79") (name "Net-(T19-Base)") (class "Default")
      (node (ref "R19") (pin "2") (pinfunction "2_2") (pintype "passive"))
      (node (ref "T19") (pin "1") (pinfunction "Base_1") (pintype "passive"))
    )
    (net (code "80") (name "Net-(T19-Collector)") (class "Default")
      (node (ref "J1") (pin "19") (pinfunction "19_19") (pintype "passive"))
      (node (ref "T19") (pin "3") (pinfunction "Collector_3") (pintype "passive"))
    )
    (net (code "81") (name "Net-(T20-Base)") (class "Default")
      (node (ref "R20") (pin "2") (pinfunction "2_2") (pintype "passive"))
      (node (ref "T20") (pin "1") (pinfunction "Base_1") (pintype "passive"))
    )
    (net (code "82") (name "Net-(T20-Collector)") (class "Default")
      (node (ref "J1") (pin "20") (pinfunction "20_20") (pintype "passive"))
      (node (ref "T20") (pin "3") (pinfunction "Collector_3") (pintype "passive"))
    )
    (net (code "83") (name "Net-(T21-Base)") (class "Default")
      (node (ref "R21") (pin "2") (pinfunction "2_2") (pintype "passive"))
      (node (ref "T21") (pin "1") (pinfunction "Base_1") (pintype "passive"))
    )
    (net (code "84") (name "Net-(T21-Collector)") (class "Default")
      (node (ref "J1") (pin "21") (pinfunction "21_21") (pintype "passive"))
      (node (ref "T21") (pin "3") (pinfunction "Collector_3") (pintype "passive"))
    )
    (net (code "85") (name "Net-(T22-Base)") (class "Default")
      (node (ref "R22") (pin "2") (pinfunction "2_2") (pintype "passive"))
      (node (ref "T22") (pin "1") (pinfunction "Base_1") (pintype "passive"))
    )
    (net (code "86") (name "Net-(T22-Collector)") (class "Default")
      (node (ref "J1") (pin "22") (pinfunction "22_22") (pintype "passive"))
      (node (ref "T22") (pin "3") (pinfunction "Collector_3") (pintype "passive"))
    )
    (net (code "87") (name "Net-(T23-Base)") (class "Default")
      (node (ref "R23") (pin "1") (pinfunction "1_1") (pintype "passive"))
      (node (ref "T23") (pin "1") (pinfunction "Base_1") (pintype "passive"))
    )
    (net (code "88") (name "Net-(T23-Collector)") (class "Default")
      (node (ref "J1") (pin "23") (pinfunction "23_23") (pintype "passive"))
      (node (ref "T23") (pin "3") (pinfunction "Collector_3") (pintype "passive"))
    )
    (net (code "89") (name "Net-(T24-Base)") (class "Default")
      (node (ref "R24") (pin "2") (pinfunction "2_2") (pintype "passive"))
      (node (ref "T24") (pin "1") (pinfunction "Base_1") (pintype "passive"))
    )
    (net (code "90") (name "Net-(T24-Collector)") (class "Default")
      (node (ref "J1") (pin "24") (pinfunction "24_24") (pintype "passive"))
      (node (ref "T24") (pin "3") (pinfunction "Collector_3") (pintype "passive"))
    )
    (net (code "91") (name "Net-(T25-Base)") (class "Default")
      (node (ref "R25") (pin "2") (pinfunction "2_2") (pintype "passive"))
      (node (ref "T25") (pin "1") (pinfunction "Base_1") (pintype "passive"))
    )
    (net (code "92") (name "Net-(T25-Collector)") (class "Default")
      (node (ref "J1") (pin "25") (pinfunction "25_25") (pintype "passive"))
      (node (ref "T25") (pin "3") (pinfunction "Collector_3") (pintype "passive"))
    )
    (net (code "93") (name "Net-(T26-Base)") (class "Default")
      (node (ref "R26") (pin "2") (pinfunction "2_2") (pintype "passive"))
      (node (ref "T26") (pin "1") (pinfunction "Base_1") (pintype "passive"))
    )
    (net (code "94") (name "Net-(T26-Collector)") (class "Default")
      (node (ref "J1") (pin "26") (pinfunction "26_26") (pintype "passive"))
      (node (ref "T26") (pin "3") (pinfunction "Collector_3") (pintype "passive"))
    )
    (net (code "95") (name "Net-(T27-Base)") (class "Default")
      (node (ref "R27") (pin "2") (pinfunction "2_2") (pintype "passive"))
      (node (ref "T27") (pin "1") (pinfunction "Base_1") (pintype "passive"))
    )
    (net (code "96") (name "Net-(T27-Collector)") (class "Default")
      (node (ref "J1") (pin "27") (pinfunction "27_27") (pintype "passive"))
      (node (ref "T27") (pin "3") (pinfunction "Collector_3") (pintype "passive"))
    )
    (net (code "97") (name "Net-(T28-Base)") (class "Default")
      (node (ref "R28") (pin "1") (pinfunction "1_1") (pintype "passive"))
      (node (ref "T28") (pin "1") (pinfunction "Base_1") (pintype "passive"))
    )
    (net (code "98") (name "Net-(T28-Collector)") (class "Default")
      (node (ref "J1") (pin "28") (pinfunction "28_28") (pintype "passive"))
      (node (ref "T28") (pin "3") (pinfunction "Collector_3") (pintype "passive"))
    )
    (net (code "99") (name "Net-(T29-Base)") (class "Default")
      (node (ref "R29") (pin "2") (pinfunction "2_2") (pintype "passive"))
      (node (ref "T29") (pin "1") (pinfunction "Base_1") (pintype "passive"))
    )
    (net (code "100") (name "Net-(T29-Collector)") (class "Default")
      (node (ref "J1") (pin "29") (pinfunction "29_29") (pintype "passive"))
      (node (ref "T29") (pin "3") (pinfunction "Collector_3") (pintype "passive"))
    )
    (net (code "101") (name "Net-(U1-NRST)") (class "Default")
      (node (ref "J2") (pin "4") (pinfunction "4_4") (pintype "passive"))
      (node (ref "R30") (pin "2") (pinfunction "2_2") (pintype "passive"))
      (node (ref "U1") (pin "7") (pinfunction "NRST_7") (pintype "passive"))
    )
    (net (code "102") (name "Net-(U1-OSC32_IN)") (class "Default")
      (node (ref "C2") (pin "2") (pinfunction "2_2") (pintype "passive"))
      (node (ref "Q1") (pin "1") (pinfunction "1_1") (pintype "passive"))
      (node (ref "U1") (pin "3") (pinfunction "OSC32_IN_3") (pintype "passive"))
    )
    (net (code "103") (name "Net-(U1-OSC32_OUT)") (class "Default")
      (node (ref "C3") (pin "2") (pinfunction "2_2") (pintype "passive"))
      (node (ref "Q1") (pin "2") (pinfunction "2_2") (pintype "passive"))
      (node (ref "U1") (pin "4") (pinfunction "OSC32_OUT_4") (pintype "passive"))
    )
    (net (code "104") (name "Net-(U1-SWCLK)") (class "Default")
      (node (ref "J2") (pin "3") (pinfunction "3_3") (pintype "passive"))
      (node (ref "U1") (pin "49") (pinfunction "SWCLK_49") (pintype "passive"))
    )
    (net (code "105") (name "Net-(U1-SWDIO)") (class "Default")
      (node (ref "J2") (pin "2") (pinfunction "2_2") (pintype "passive"))
      (node (ref "U1") (pin "46") (pinfunction "SWDIO_46") (pintype "passive"))
    )
    (net (code "106") (name "Net-(U4A-Out)") (class "Default")
      (node (ref "U4") (pin "9") (pinfunction "Out_9") (pintype "passive"))
      (node (ref "U5") (pin "14") (pinfunction "IN_14") (pintype "passive"))
    )
    (net (code "107") (name "Net-(U5A-Out)") (class "Default")
      (node (ref "U5") (pin "9") (pinfunction "Out_9") (pintype "passive"))
      (node (ref "U6") (pin "14") (pinfunction "IN_14") (pintype "passive"))
    )
    (net (code "108") (name "Net-(U6A-Out)") (class "Default")
      (node (ref "U6") (pin "9") (pinfunction "Out_9") (pintype "passive"))
      (node (ref "U7") (pin "14") (pinfunction "IN_14") (pintype "passive"))
    )
    (net (code "109") (name "unconnected-(U1-PA0-Pad14)") (class "Default")
      (node (ref "U1") (pin "14") (pinfunction "PA0_14") (pintype "passive"))
    )
    (net (code "110") (name "unconnected-(U1-PA8-Pad41)") (class "Default")
      (node (ref "U1") (pin "41") (pinfunction "PA8_41") (pintype "passive"))
    )
    (net (code "111") (name "unconnected-(U1-PA9-Pad42)") (class "Default")
      (node (ref "U1") (pin "42") (pinfunction "PA9_42") (pintype "passive"))
    )
    (net (code "112") (name "unconnected-(U1-PA10-Pad43)") (class "Default")
      (node (ref "U1") (pin "43") (pinfunction "PA10_43") (pintype "passive"))
    )
    (net (code "113") (name "unconnected-(U1-PA11-Pad44)") (class "Default")
      (node (ref "U1") (pin "44") (pinfunction "PA11_44") (pintype "passive"))
    )
    (net (code "114") (name "unconnected-(U1-PA12-Pad45)") (class "Default")
      (node (ref "U1") (pin "45") (pinfunction "PA12_45") (pintype "passive"))
    )
    (net (code "115") (name "unconnected-(U1-PA15-Pad50)") (class "Default")
      (node (ref "U1") (pin "50") (pinfunction "PA15_50") (pintype "passive"))
    )
    (net (code "116") (name "unconnected-(U1-PB1-Pad27)") (class "Default")
      (node (ref "U1") (pin "27") (pinfunction "PB1_27") (pintype "passive"))
    )
    (net (code "117") (name "unconnected-(U1-PB3-Pad55)") (class "Default")
      (node (ref "U1") (pin "55") (pinfunction "PB3_55") (pintype "passive"))
    )
    (net (code "118") (name "unconnected-(U1-PB4-Pad56)") (class "Default")
      (node (ref "U1") (pin "56") (pinfunction "PB4_56") (pintype "passive"))
    )
    (net (code "119") (name "unconnected-(U1-PB5-Pad57)") (class "Default")
      (node (ref "U1") (pin "57") (pinfunction "PB5_57") (pintype "passive"))
    )
    (net (code "120") (name "unconnected-(U1-PB6-Pad58)") (class "Default")
      (node (ref "U1") (pin "58") (pinfunction "PB6_58") (pintype "passive"))
    )
    (net (code "121") (name "unconnected-(U1-PB7-Pad59)") (class "Default")
      (node (ref "U1") (pin "59") (pinfunction "PB7_59") (pintype "passive"))
    )
    (net (code "122") (name "unconnected-(U1-PB8-Pad61)") (class "Default")
      (node (ref "U1") (pin "61") (pinfunction "PB8_61") (pintype "passive"))
    )
    (net (code "123") (name "unconnected-(U1-PB9-Pad62)") (class "Default")
      (node (ref "U1") (pin "62") (pinfunction "PB9_62") (pintype "passive"))
    )
    (net (code "124") (name "unconnected-(U1-PB10-Pad29)") (class "Default")
      (node (ref "U1") (pin "29") (pinfunction "PB10_29") (pintype "passive"))
    )
    (net (code "125") (name "unconnected-(U1-PB11-Pad30)") (class "Default")
      (node (ref "U1") (pin "30") (pinfunction "PB11_30") (pintype "passive"))
    )
    (net (code "126") (name "unconnected-(U1-PB12-Pad33)") (class "Default")
      (node (ref "U1") (pin "33") (pinfunction "PB12_33") (pintype "passive"))
    )
    (net (code "127") (name "unconnected-(U1-PB13-Pad34)") (class "Default")
      (node (ref "U1") (pin "34") (pinfunction "PB13_34") (pintype "passive"))
    )
    (net (code "128") (name "unconnected-(U1-PB14-Pad35)") (class "Default")
      (node (ref "U1") (pin "35") (pinfunction "PB14_35") (pintype "passive"))
    )
    (net (code "129") (name "unconnected-(U1-PB15-Pad36)") (class "Default")
      (node (ref "U1") (pin "36") (pinfunction "PB15_36") (pintype "passive"))
    )
    (net (code "130") (name "unconnected-(U1-PC0-Pad8)") (class "Default")
      (node (ref "U1") (pin "8") (pinfunction "PC0_8") (pintype "passive"))
    )
    (net (code "131") (name "unconnected-(U1-PC1-Pad9)") (class "Default")
      (node (ref "U1") (pin "9") (pinfunction "PC1_9") (pintype "passive"))
    )
    (net (code "132") (name "unconnected-(U1-PC2-Pad10)") (class "Default")
      (node (ref "U1") (pin "10") (pinfunction "PC2_10") (pintype "passive"))
    )
    (net (code "133") (name "unconnected-(U1-PC3-Pad11)") (class "Default")
      (node (ref "U1") (pin "11") (pinfunction "PC3_11") (pintype "passive"))
    )
    (net (code "134") (name "unconnected-(U1-PC5-Pad25)") (class "Default")
      (node (ref "U1") (pin "25") (pinfunction "PC5_25") (pintype "passive"))
    )
    (net (code "135") (name "unconnected-(U1-PC6-Pad37)") (class "Default")
      (node (ref "U1") (pin "37") (pinfunction "PC6_37") (pintype "passive"))
    )
    (net (code "136") (name "unconnected-(U1-PC7-Pad38)") (class "Default")
      (node (ref "U1") (pin "38") (pinfunction "PC7_38") (pintype "passive"))
    )
    (net (code "137") (name "unconnected-(U1-PC8-Pad39)") (class "Default")
      (node (ref "U1") (pin "39") (pinfunction "PC8_39") (pintype "passive"))
    )
    (net (code "138") (name "unconnected-(U1-PC9-Pad40)") (class "Default")
      (node (ref "U1") (pin "40") (pinfunction "PC9_40") (pintype "passive"))
    )
    (net (code "139") (name "unconnected-(U1-PC10-Pad51)") (class "Default")
      (node (ref "U1") (pin "51") (pinfunction "PC10_51") (pintype "passive"))
    )
    (net (code "140") (name "unconnected-(U1-PC11-Pad52)") (class "Default")
      (node (ref "U1") (pin "52") (pinfunction "PC11_52") (pintype "passive"))
    )
    (net (code "141") (name "unconnected-(U1-PC12-Pad53)") (class "Default")
      (node (ref "U1") (pin "53") (pinfunction "PC12_53") (pintype "passive"))
    )
    (net (code "142") (name "unconnected-(U1-PC13-Pad2)") (class "Default")
      (node (ref "U1") (pin "2") (pinfunction "PC13_2") (pintype "passive"))
    )
    (net (code "143") (name "unconnected-(U1-PD0-Pad5)") (class "Default")
      (node (ref "U1") (pin "5") (pinfunction "PD0_5") (pintype "passive"))
    )
    (net (code "144") (name "unconnected-(U1-PD1-Pad6)") (class "Default")
      (node (ref "U1") (pin "6") (pinfunction "PD1_6") (pintype "passive"))
    )
    (net (code "145") (name "unconnected-(U1-PD2-Pad54)") (class "Default")
      (node (ref "U1") (pin "54") (pinfunction "PD2_54") (pintype "passive"))
    )
    (net (code "146") (name "unconnected-(U7A-Out-Pad9)") (class "Default")
      (node (ref "U7") (pin "9") (pinfunction "Out_9") (pintype "passive"))
    )
    (net (code "147") (name "unconnected-(U7A-QF-Pad5)") (class "Default")
      (node (ref "U7") (pin "5") (pinfunction "QF_5") (pintype "passive"))
    )
    (net (code "148") (name "unconnected-(U7A-QG-Pad6)") (class "Default")
      (node (ref "U7") (pin "6") (pinfunction "QG_6") (pintype "passive"))
    )
    (net (code "149") (name "unconnected-(U7A-QH-Pad7)") (class "Default")
      (node (ref "U7") (pin "7") (pinfunction "QH_7") (pintype "passive"))
    )
  )
)
